# schematic.net
KiCad netlist of a schematic drawn in Altium Designer
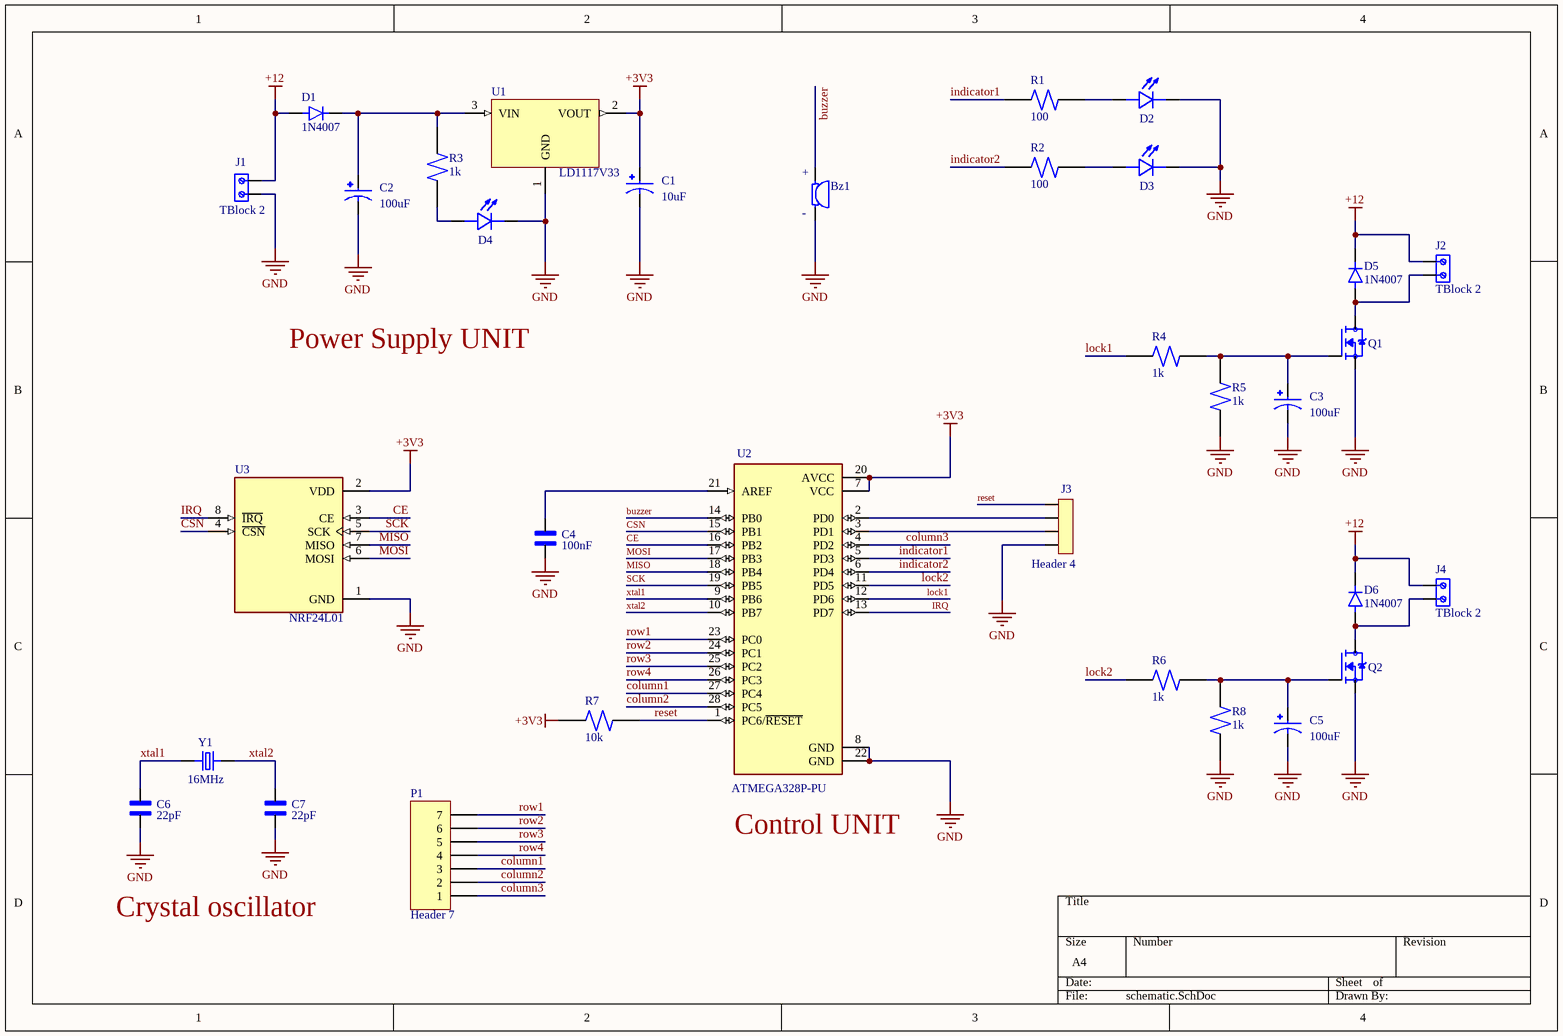
[diagram p0: schematic.SchDoc]

(export (version "E")
  (design (tool "Eeschema 10.0.6"))
  (components
    (comp (ref "Bz1")
      (value "AI-1223-TWT-12V-R")
      (footprint "XDCR_AI-1223-TWT-12V-R")
      (description "ELECTRO-MECHANICAL AUDIO INDICATOR")
      (fields (field (name "MF") "PUI Audio,"))
      (libsource (lib "Installed library") (part "Buzzer"))
    )
    (comp (ref "C1")
      (value "10uF")
      (footprint "CAPPRD500W50D500H1100")
      (description "FS-A")
      (fields (field (name "MF") "{'manufacturer': u'Panasonic'}") (field (name "MP") "EEUFS0J221B"))
      (libsource (lib "") (part "Electrolytic capacitor_1"))
    )
    (comp (ref "C2")
      (value "100uF")
      (footprint "CAPPRD500W50D500H1100")
      (description "FS-A")
      (fields (field (name "MF") "{'manufacturer': u'Panasonic'}") (field (name "MP") "EEUFS0J221B"))
      (libsource (lib "Installed library") (part "Electrolytic capacitor"))
    )
    (comp (ref "C3")
      (value "100uF")
      (footprint "CAPPRD500W50D500H1100")
      (description "FS-A")
      (fields (field (name "MF") "{'manufacturer': u'Panasonic'}") (field (name "MP") "EEUFS0J221B"))
      (libsource (lib "") (part "Electrolytic capacitor_1"))
    )
    (comp (ref "C4")
      (value "100nF")
      (footprint "CAPRB500W50L450T300H550")
      (description "2200 pF Â±10% 250V Ceramic Capacitor X7R Radial")
      (fields (field (name "DIGI-KEY_PART_NUMBER") "445-173386-1-ND") (field (name "MF") "TDK"))
      (libsource (lib "Installed library") (part "Ceramic capacitor"))
    )
    (comp (ref "C5")
      (value "100uF")
      (footprint "CAPPRD500W50D500H1100")
      (description "FS-A")
      (fields (field (name "MF") "{'manufacturer': u'Panasonic'}") (field (name "MP") "EEUFS0J221B"))
      (libsource (lib "") (part "Electrolytic capacitor_1"))
    )
    (comp (ref "C6")
      (value "22pF")
      (footprint "CAPRB500W50L450T300H550")
      (description "2200 pF Â±10% 250V Ceramic Capacitor X7R Radial")
      (fields (field (name "DIGI-KEY_PART_NUMBER") "445-173386-1-ND") (field (name "MF") "TDK"))
      (libsource (lib "Installed library") (part "Ceramic capacitor"))
    )
    (comp (ref "C7")
      (value "22pF")
      (footprint "CAPRB500W50L450T300H550")
      (description "2200 pF Â±10% 250V Ceramic Capacitor X7R Radial")
      (fields (field (name "DIGI-KEY_PART_NUMBER") "445-173386-1-ND") (field (name "MF") "TDK"))
      (libsource (lib "Installed library") (part "Ceramic capacitor"))
    )
    (comp (ref "D1")
      (value "1N4007")
      (footprint "DIOAD1060W80L520D270")
      (description "Diode Switching 1KV 1A 2-Pin DO-41")
      (libsource (lib "Components") (part "1N4007"))
    )
    (comp (ref "D2")
      (value "L08R5000Q1")
      (footprint "LEDRD254W57D500H1070")
      (description "LED, Orange, Through Hole, T-1 3/4 (5mm), 30 mA, 2.1 V, 635 nm")
      (fields (field (name "MF") "{'manufacturer': u'LED Technology'}"))
      (libsource (lib "Installed library") (part "LED"))
    )
    (comp (ref "D3")
      (value "L08R5000Q1")
      (footprint "LEDRD254W57D500H1070")
      (description "LED, Orange, Through Hole, T-1 3/4 (5mm), 30 mA, 2.1 V, 635 nm")
      (fields (field (name "MF") "{'manufacturer': u'LED Technology'}"))
      (libsource (lib "Installed library") (part "LED"))
    )
    (comp (ref "D4")
      (value "L08R5000Q1")
      (footprint "LEDRD254W57D500H1070")
      (description "LED, Orange, Through Hole, T-1 3/4 (5mm), 30 mA, 2.1 V, 635 nm")
      (fields (field (name "MF") "{'manufacturer': u'LED Technology'}"))
      (libsource (lib "Installed library") (part "LED"))
    )
    (comp (ref "D5")
      (value "1N4007")
      (footprint "DIOAD1060W80L520D270")
      (description "Diode Switching 1KV 1A 2-Pin DO-41")
      (libsource (lib "Components") (part "1N4007"))
    )
    (comp (ref "D6")
      (value "1N4007")
      (footprint "DIOAD1060W80L520D270")
      (description "Diode Switching 1KV 1A 2-Pin DO-41")
      (libsource (lib "Components") (part "1N4007"))
    )
    (comp (ref "J1")
      (value "TBlock 2")
      (footprint "691111710002")
      (description "2 Position Wire to Board Terminal Block Horizontal with Board 0.197 _5.00mm_ Through Hole")
      (fields (field (name "MP") "691111710002") (field (name "MF") "Wurth Electronics"))
      (libsource (lib "Installed library") (part "Terminal Block - 2Pins"))
    )
    (comp (ref "J2")
      (value "TBlock 2")
      (footprint "691111710002")
      (description "2 Position Wire to Board Terminal Block Horizontal with Board 0.197 _5.00mm_ Through Hole")
      (fields (field (name "MP") "691111710002") (field (name "MF") "Wurth Electronics"))
      (libsource (lib "Installed library") (part "Terminal Block - 2Pins"))
    )
    (comp (ref "J3")
      (value "Header 4")
      (footprint "SULLINS_PPTC041LFBN-RC")
      (description "4 Position Header Connector Through Hole")
      (fields (field (name "MP") "PPTC041LFBN-RC") (field (name "MF") "Sullins Connector"))
      (libsource (lib "Installed library") (part "Female header - 4Pins"))
    )
    (comp (ref "J4")
      (value "TBlock 2")
      (footprint "691111710002")
      (description "2 Position Wire to Board Terminal Block Horizontal with Board 0.197 _5.00mm_ Through Hole")
      (fields (field (name "MP") "691111710002") (field (name "MF") "Wurth Electronics"))
      (libsource (lib "Installed library") (part "Terminal Block - 2Pins"))
    )
    (comp (ref "P1")
      (value "Header 7")
      (footprint "HDR1X7")
      (description "Header, 7-Pin")
      (fields (field (name "PUBLISHER") "Altium Limited"))
      (libsource (lib "Miscellaneous Connectors") (part "Header 7"))
    )
    (comp (ref "Q1")
      (value "N-Channel mosfet")
      (footprint "TO254P1052X465X1989-3")
      (description "N-Channel 100V 22A (Tc) 85W (Tc) Through Hole TO-220AB")
      (fields (field (name "MP") "IRF540"))
      (libsource (lib "Installed library") (part "IRF540"))
    )
    (comp (ref "Q2")
      (value "N-Channel mosfet")
      (footprint "TO254P1052X465X1989-3")
      (description "N-Channel 100V 22A (Tc) 85W (Tc) Through Hole TO-220AB")
      (fields (field (name "MP") "IRF540"))
      (libsource (lib "Installed library") (part "IRF540"))
    )
    (comp (ref "R1")
      (value "100")
      (footprint "RESAD1100W55L680D260")
      (description "(MFR-25FBF52-10K) 10,2 kOhm bei 1% 0,25W, 1/4W Durchbohrlochwiderstand Axial Metal Film")
      (fields (field (name "DIGI-KEY_PART_NUMBER") "10.2KXBK-ND") (field (name "MF") "Yageo"))
      (libsource (lib "Installed library") (part "Resistor (0.25W)"))
    )
    (comp (ref "R2")
      (value "100")
      (footprint "RESAD1100W55L680D260")
      (description "(MFR-25FBF52-10K) 10,2 kOhm bei 1% 0,25W, 1/4W Durchbohrlochwiderstand Axial Metal Film")
      (fields (field (name "DIGI-KEY_PART_NUMBER") "10.2KXBK-ND") (field (name "MF") "Yageo"))
      (libsource (lib "Installed library") (part "Resistor (0.25W)"))
    )
    (comp (ref "R3")
      (value "1k")
      (footprint "RESAD1100W55L680D260")
      (description "(MFR-25FBF52-10K) 10,2 kOhm bei 1% 0,25W, 1/4W Durchbohrlochwiderstand Axial Metal Film")
      (fields (field (name "DIGI-KEY_PART_NUMBER") "10.2KXBK-ND") (field (name "MF") "Yageo"))
      (libsource (lib "Installed library") (part "Resistor (0.25W)"))
    )
    (comp (ref "R4")
      (value "1k")
      (footprint "RESAD1100W55L680D260")
      (description "(MFR-25FBF52-10K) 10,2 kOhm bei 1% 0,25W, 1/4W Durchbohrlochwiderstand Axial Metal Film")
      (fields (field (name "DIGI-KEY_PART_NUMBER") "10.2KXBK-ND") (field (name "MF") "Yageo"))
      (libsource (lib "Installed library") (part "Resistor (0.25W)"))
    )
    (comp (ref "R5")
      (value "1k")
      (footprint "RESAD1100W55L680D260")
      (description "(MFR-25FBF52-10K) 10,2 kOhm bei 1% 0,25W, 1/4W Durchbohrlochwiderstand Axial Metal Film")
      (fields (field (name "DIGI-KEY_PART_NUMBER") "10.2KXBK-ND") (field (name "MF") "Yageo"))
      (libsource (lib "Installed library") (part "Resistor (0.25W)"))
    )
    (comp (ref "R6")
      (value "1k")
      (footprint "RESAD1100W55L680D260")
      (description "(MFR-25FBF52-10K) 10,2 kOhm bei 1% 0,25W, 1/4W Durchbohrlochwiderstand Axial Metal Film")
      (fields (field (name "DIGI-KEY_PART_NUMBER") "10.2KXBK-ND") (field (name "MF") "Yageo"))
      (libsource (lib "Installed library") (part "Resistor (0.25W)"))
    )
    (comp (ref "R7")
      (value "10k")
      (footprint "RESAD1100W55L680D260")
      (description "(MFR-25FBF52-10K) 10,2 kOhm bei 1% 0,25W, 1/4W Durchbohrlochwiderstand Axial Metal Film")
      (fields (field (name "DIGI-KEY_PART_NUMBER") "10.2KXBK-ND") (field (name "MF") "Yageo"))
      (libsource (lib "Installed library") (part "Resistor (0.25W)"))
    )
    (comp (ref "R8")
      (value "1k")
      (footprint "RESAD1100W55L680D260")
      (description "(MFR-25FBF52-10K) 10,2 kOhm bei 1% 0,25W, 1/4W Durchbohrlochwiderstand Axial Metal Film")
      (fields (field (name "DIGI-KEY_PART_NUMBER") "10.2KXBK-ND") (field (name "MF") "Yageo"))
      (libsource (lib "Installed library") (part "Resistor (0.25W)"))
    )
    (comp (ref "U1")
      (value "LD1117V33")
      (footprint "TO255P1020X450X1968-3")
      (libsource (lib "Voltage regulator") (part "LD1117V33"))
    )
    (comp (ref "U2")
      (value "ATMEGA328P-PU")
      (footprint "DIP794W46P254L2967H457Q28B")
      (description "ATmega Series 20 MHz 32 KB Flash 2 KB SRAM 8-Bit Microcontroller - DIP-28")
      (libsource (lib "Installed library") (part "ATMEGA328P-PU"))
    )
    (comp (ref "U3")
      (value "NRF24L01")
      (footprint "XCVR_NRF24L01P-MODULE-PCB")
      (description "- Transceiver For Use With nRF24L01+")
      (fields (field (name "MP") "NRF24L01P-MODULE-PCB") (field (name "MF") "Nordic Semiconductor"))
      (libsource (lib "Modules") (part "NRF24L01P-MODULE-PCB"))
    )
    (comp (ref "Y1")
      (value "16MHz")
      (footprint "XTAL_ECS-160-20-4X")
      (description "CRYSTAL T/H")
      (fields (field (name "MF") "{'manufacturer': u'ECS Inc.'}") (field (name "MP") "ECS-160-S-4"))
      (libsource (lib "Installed library") (part "Crystal oscilator"))
    )
  )
  (nets
    (net (code "1") (name "+3V3") (class "Default")
      (node (ref "C1") (pin "P") (pinfunction "P_P") (pintype "passive"))
      (node (ref "R7") (pin "2") (pinfunction "2_2") (pintype "passive"))
      (node (ref "U1") (pin "2") (pinfunction "VOUT_2") (pintype "output"))
      (node (ref "U2") (pin "20") (pinfunction "AVCC_20") (pintype "power_in"))
      (node (ref "U2") (pin "7") (pinfunction "VCC_7") (pintype "power_in"))
      (node (ref "U3") (pin "2") (pinfunction "VDD_2") (pintype "power_in"))
    )
    (net (code "2") (name "+12") (class "Default")
      (node (ref "D1") (pin "A") (pinfunction "A_A") (pintype "passive"))
      (node (ref "D5") (pin "C") (pinfunction "C_C") (pintype "passive"))
      (node (ref "D6") (pin "C") (pinfunction "C_C") (pintype "passive"))
      (node (ref "J1") (pin "2") (pinfunction "2_2") (pintype "passive"))
      (node (ref "J2") (pin "1") (pinfunction "1_1") (pintype "passive"))
      (node (ref "J4") (pin "1") (pinfunction "1_1") (pintype "passive"))
    )
    (net (code "3") (name "/CE") (class "Default")
      (node (ref "U2") (pin "16") (pinfunction "PB2_16") (pintype "bidirectional"))
      (node (ref "U3") (pin "3") (pinfunction "CE_3") (pintype "input"))
    )
    (net (code "4") (name "/CSN") (class "Default")
      (node (ref "U2") (pin "15") (pinfunction "PB1_15") (pintype "bidirectional"))
      (node (ref "U3") (pin "4") (pinfunction "~{CSN}_4") (pintype "input"))
    )
    (net (code "5") (name "/IRQ") (class "Default")
      (node (ref "U2") (pin "13") (pinfunction "PD7_13") (pintype "bidirectional"))
      (node (ref "U3") (pin "8") (pinfunction "~{IRQ}_8") (pintype "input"))
    )
    (net (code "6") (name "/MISO") (class "Default")
      (node (ref "U2") (pin "18") (pinfunction "PB4_18") (pintype "bidirectional"))
      (node (ref "U3") (pin "7") (pinfunction "MISO_7") (pintype "input"))
    )
    (net (code "7") (name "/MOSI") (class "Default")
      (node (ref "U2") (pin "17") (pinfunction "PB3_17") (pintype "bidirectional"))
      (node (ref "U3") (pin "6") (pinfunction "MOSI_6") (pintype "input"))
    )
    (net (code "8") (name "/SCK") (class "Default")
      (node (ref "U2") (pin "19") (pinfunction "PB5_19") (pintype "bidirectional"))
      (node (ref "U3") (pin "5") (pinfunction "SCK_5") (pintype "input"))
    )
    (net (code "9") (name "/buzzer") (class "Default")
      (node (ref "Bz1") (pin "P") (pinfunction "POS_P") (pintype "passive"))
      (node (ref "U2") (pin "14") (pinfunction "PB0_14") (pintype "bidirectional"))
    )
    (net (code "10") (name "/column1") (class "Default")
      (node (ref "P1") (pin "3") (pinfunction "3_3") (pintype "passive"))
      (node (ref "U2") (pin "27") (pinfunction "PC4_27") (pintype "bidirectional"))
    )
    (net (code "11") (name "/column2") (class "Default")
      (node (ref "P1") (pin "2") (pinfunction "2_2") (pintype "passive"))
      (node (ref "U2") (pin "28") (pinfunction "PC5_28") (pintype "bidirectional"))
    )
    (net (code "12") (name "/column3") (class "Default")
      (node (ref "P1") (pin "1") (pinfunction "1_1") (pintype "passive"))
      (node (ref "U2") (pin "4") (pinfunction "PD2_4") (pintype "bidirectional"))
    )
    (net (code "13") (name "/indicator1") (class "Default")
      (node (ref "R1") (pin "2") (pinfunction "2_2") (pintype "passive"))
      (node (ref "U2") (pin "5") (pinfunction "PD3_5") (pintype "bidirectional"))
    )
    (net (code "14") (name "/indicator2") (class "Default")
      (node (ref "R2") (pin "2") (pinfunction "2_2") (pintype "passive"))
      (node (ref "U2") (pin "6") (pinfunction "PD4_6") (pintype "bidirectional"))
    )
    (net (code "15") (name "/lock1") (class "Default")
      (node (ref "R4") (pin "2") (pinfunction "2_2") (pintype "passive"))
      (node (ref "U2") (pin "12") (pinfunction "PD6_12") (pintype "bidirectional"))
    )
    (net (code "16") (name "/lock2") (class "Default")
      (node (ref "R6") (pin "2") (pinfunction "2_2") (pintype "passive"))
      (node (ref "U2") (pin "11") (pinfunction "PD5_11") (pintype "bidirectional"))
    )
    (net (code "17") (name "/reset") (class "Default")
      (node (ref "J3") (pin "4") (pinfunction "4_4") (pintype "passive"))
      (node (ref "R7") (pin "1") (pinfunction "1_1") (pintype "passive"))
      (node (ref "U2") (pin "1") (pinfunction "PC6/~{RESET}_1") (pintype "bidirectional"))
    )
    (net (code "18") (name "/row1") (class "Default")
      (node (ref "P1") (pin "7") (pinfunction "7_7") (pintype "passive"))
      (node (ref "U2") (pin "23") (pinfunction "PC0_23") (pintype "bidirectional"))
    )
    (net (code "19") (name "/row2") (class "Default")
      (node (ref "P1") (pin "6") (pinfunction "6_6") (pintype "passive"))
      (node (ref "U2") (pin "24") (pinfunction "PC1_24") (pintype "bidirectional"))
    )
    (net (code "20") (name "/row3") (class "Default")
      (node (ref "P1") (pin "5") (pinfunction "5_5") (pintype "passive"))
      (node (ref "U2") (pin "25") (pinfunction "PC2_25") (pintype "bidirectional"))
    )
    (net (code "21") (name "/row4") (class "Default")
      (node (ref "P1") (pin "4") (pinfunction "4_4") (pintype "passive"))
      (node (ref "U2") (pin "26") (pinfunction "PC3_26") (pintype "bidirectional"))
    )
    (net (code "22") (name "/xtal1") (class "Default")
      (node (ref "C6") (pin "1") (pinfunction "1_1") (pintype "passive"))
      (node (ref "U2") (pin "9") (pinfunction "PB6_9") (pintype "bidirectional"))
      (node (ref "Y1") (pin "1") (pinfunction "1_1") (pintype "passive"))
    )
    (net (code "23") (name "/xtal2") (class "Default")
      (node (ref "C7") (pin "1") (pinfunction "1_1") (pintype "passive"))
      (node (ref "U2") (pin "10") (pinfunction "PB7_10") (pintype "bidirectional"))
      (node (ref "Y1") (pin "2") (pinfunction "2_2") (pintype "passive"))
    )
    (net (code "24") (name "GND") (class "Default")
      (node (ref "Bz1") (pin "N") (pinfunction "NEG_N") (pintype "passive"))
      (node (ref "C1") (pin "N") (pinfunction "N_N") (pintype "passive"))
      (node (ref "C2") (pin "N") (pinfunction "N_N") (pintype "passive"))
      (node (ref "C3") (pin "N") (pinfunction "N_N") (pintype "passive"))
      (node (ref "C4") (pin "2") (pinfunction "2_2") (pintype "passive"))
      (node (ref "C5") (pin "N") (pinfunction "N_N") (pintype "passive"))
      (node (ref "C6") (pin "2") (pinfunction "2_2") (pintype "passive"))
      (node (ref "C7") (pin "2") (pinfunction "2_2") (pintype "passive"))
      (node (ref "D2") (pin "C") (pinfunction "C_C") (pintype "passive"))
      (node (ref "D3") (pin "C") (pinfunction "C_C") (pintype "passive"))
      (node (ref "D4") (pin "C") (pinfunction "C_C") (pintype "passive"))
      (node (ref "J1") (pin "1") (pinfunction "1_1") (pintype "passive"))
      (node (ref "J3") (pin "1") (pinfunction "1_1") (pintype "passive"))
      (node (ref "Q1") (pin "3") (pinfunction "S_3") (pintype "passive"))
      (node (ref "Q2") (pin "3") (pinfunction "S_3") (pintype "passive"))
      (node (ref "R5") (pin "1") (pinfunction "1_1") (pintype "passive"))
      (node (ref "R8") (pin "1") (pinfunction "1_1") (pintype "passive"))
      (node (ref "U1") (pin "1") (pinfunction "GND_1") (pintype "passive"))
      (node (ref "U2") (pin "22") (pinfunction "GND_22") (pintype "power_in"))
      (node (ref "U2") (pin "8") (pinfunction "GND_8") (pintype "power_in"))
      (node (ref "U3") (pin "1") (pinfunction "GND_1") (pintype "power_in"))
    )
    (net (code "25") (name "Net-(D2-PadA)") (class "Default")
      (node (ref "D2") (pin "A") (pinfunction "A_A") (pintype "passive"))
      (node (ref "R1") (pin "1") (pinfunction "1_1") (pintype "passive"))
    )
    (net (code "26") (name "Net-(D3-PadA)") (class "Default")
      (node (ref "D3") (pin "A") (pinfunction "A_A") (pintype "passive"))
      (node (ref "R2") (pin "1") (pinfunction "1_1") (pintype "passive"))
    )
    (net (code "27") (name "Net-(D4-PadA)") (class "Default")
      (node (ref "D4") (pin "A") (pinfunction "A_A") (pintype "passive"))
      (node (ref "R3") (pin "1") (pinfunction "1_1") (pintype "passive"))
    )
    (net (code "28") (name "Net-(Q1-D)") (class "Default")
      (node (ref "D5") (pin "A") (pinfunction "A_A") (pintype "passive"))
      (node (ref "J2") (pin "2") (pinfunction "2_2") (pintype "passive"))
      (node (ref "Q1") (pin "2") (pinfunction "D_2") (pintype "passive"))
    )
    (net (code "29") (name "Net-(Q1-G)") (class "Default")
      (node (ref "C3") (pin "P") (pinfunction "P_P") (pintype "passive"))
      (node (ref "Q1") (pin "1") (pinfunction "G_1") (pintype "passive"))
      (node (ref "R4") (pin "1") (pinfunction "1_1") (pintype "passive"))
      (node (ref "R5") (pin "2") (pinfunction "2_2") (pintype "passive"))
    )
    (net (code "30") (name "Net-(Q2-D)") (class "Default")
      (node (ref "D6") (pin "A") (pinfunction "A_A") (pintype "passive"))
      (node (ref "J4") (pin "2") (pinfunction "2_2") (pintype "passive"))
      (node (ref "Q2") (pin "2") (pinfunction "D_2") (pintype "passive"))
    )
    (net (code "31") (name "Net-(Q2-G)") (class "Default")
      (node (ref "C5") (pin "P") (pinfunction "P_P") (pintype "passive"))
      (node (ref "Q2") (pin "1") (pinfunction "G_1") (pintype "passive"))
      (node (ref "R6") (pin "1") (pinfunction "1_1") (pintype "passive"))
      (node (ref "R8") (pin "2") (pinfunction "2_2") (pintype "passive"))
    )
    (net (code "32") (name "Net-(U1-VIN)") (class "Default")
      (node (ref "C2") (pin "P") (pinfunction "P_P") (pintype "passive"))
      (node (ref "D1") (pin "C") (pinfunction "C_C") (pintype "passive"))
      (node (ref "R3") (pin "2") (pinfunction "2_2") (pintype "passive"))
      (node (ref "U1") (pin "3") (pinfunction "VIN_3") (pintype "input"))
    )
    (net (code "33") (name "Net-(U2-AREF)") (class "Default")
      (node (ref "C4") (pin "1") (pinfunction "1_1") (pintype "passive"))
      (node (ref "U2") (pin "21") (pinfunction "AREF_21") (pintype "input"))
    )
    (net (code "34") (name "Net-(U2-PD0)") (class "Default")
      (node (ref "J3") (pin "3") (pinfunction "3_3") (pintype "passive"))
      (node (ref "U2") (pin "2") (pinfunction "PD0_2") (pintype "bidirectional"))
    )
    (net (code "35") (name "Net-(U2-PD1)") (class "Default")
      (node (ref "J3") (pin "2") (pinfunction "2_2") (pintype "passive"))
      (node (ref "U2") (pin "3") (pinfunction "PD1_3") (pintype "bidirectional"))
    )
  )
)
